# Connectors.net
KiCad netlist of a schematic drawn in Altium Designer
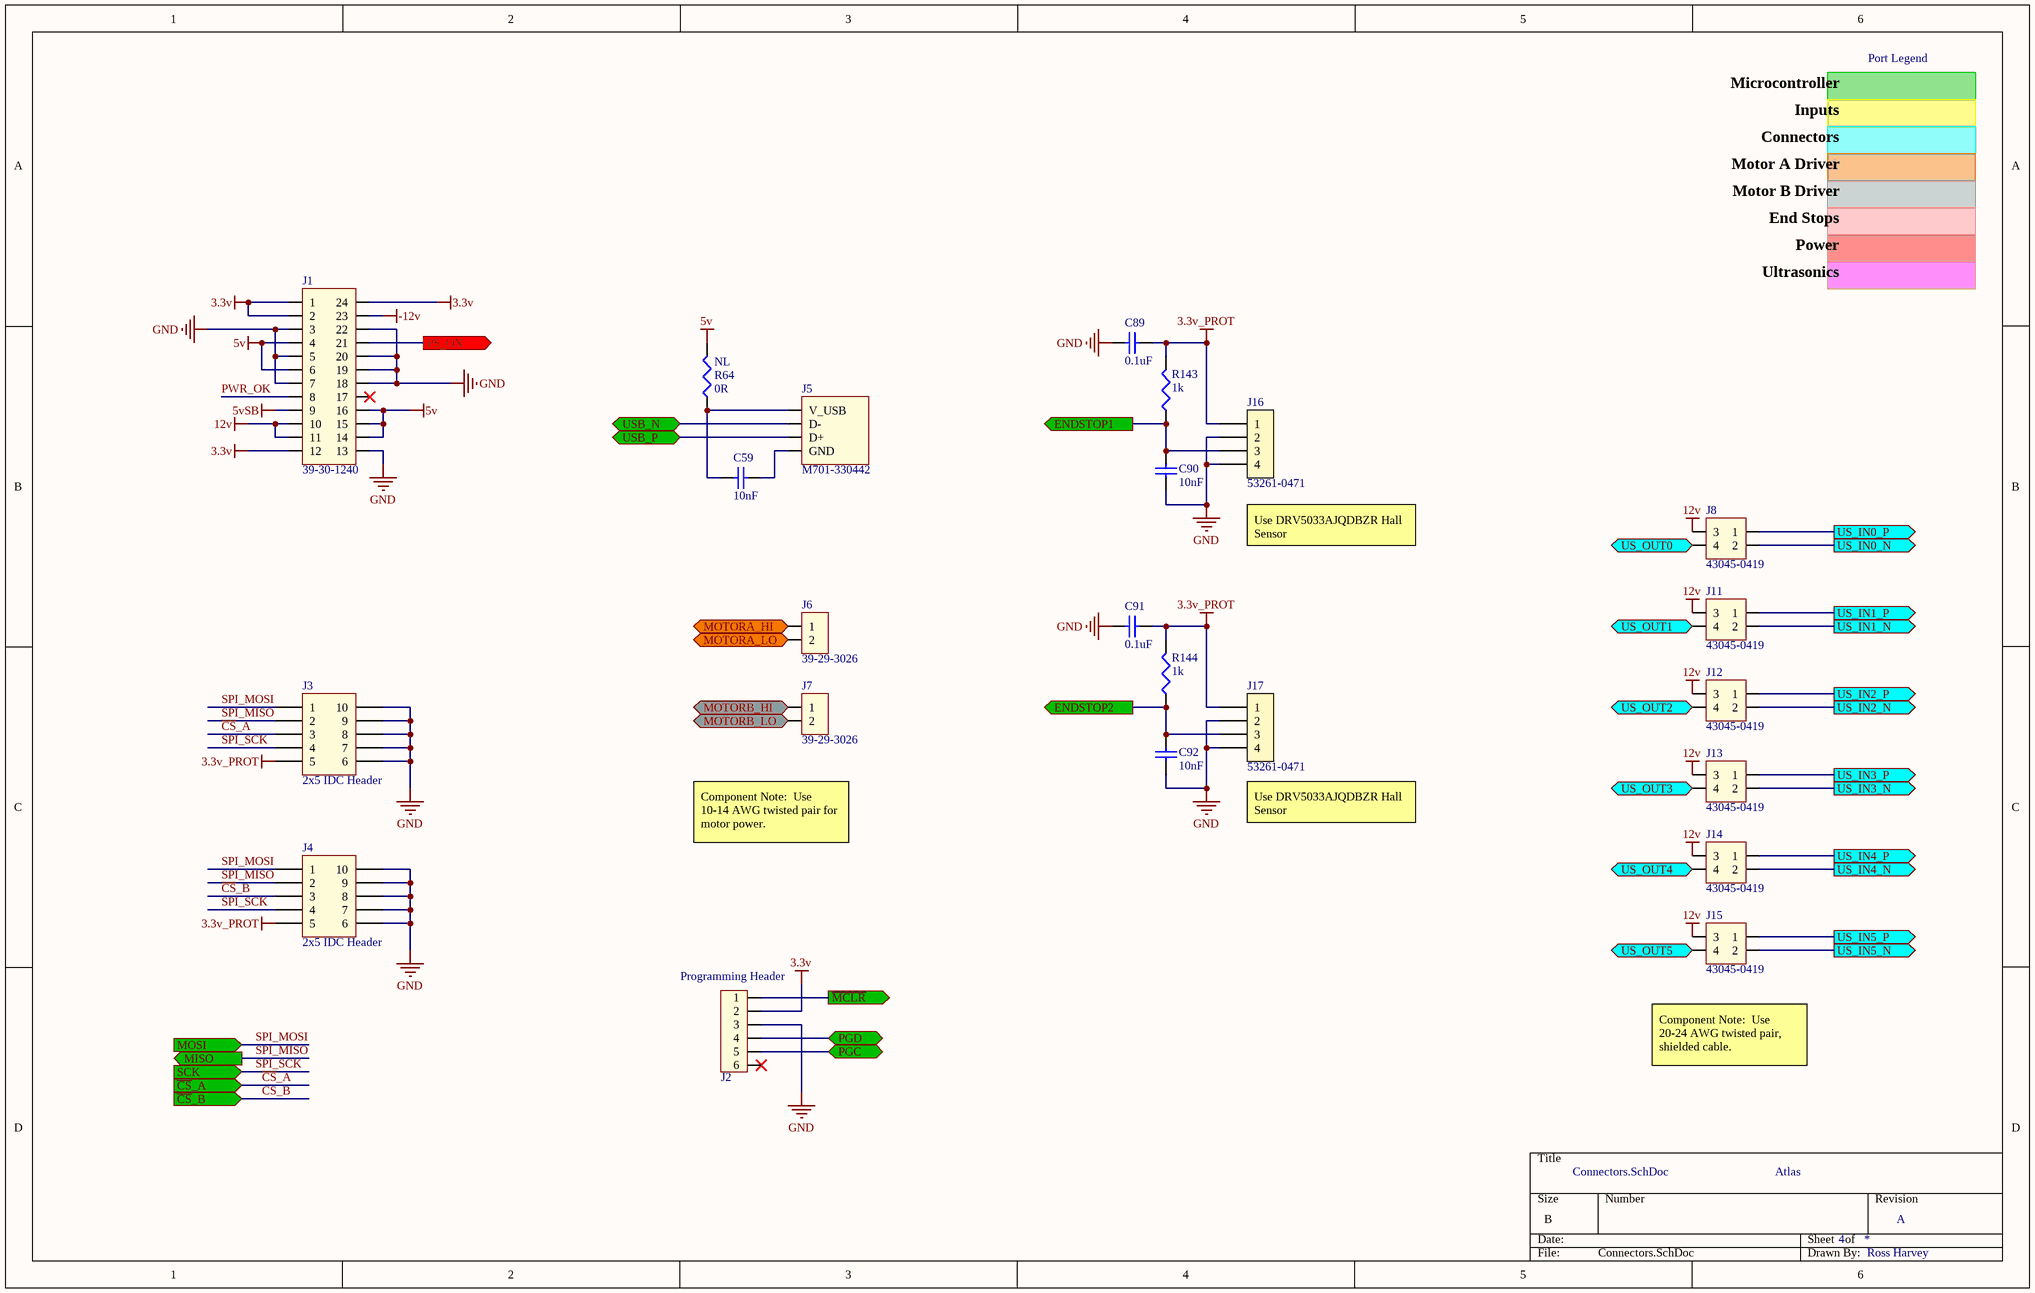
[diagram p0: Connectors.SchDoc]

(export (version "E")
  (design (tool "Eeschema 10.0.6"))
  (components
    (comp (ref "C59") (value "10nF") (footprint "CAP0603W") (libsource (lib "Altium Library") (part "10nF")))
    (comp (ref "C89")
      (value "0.1uF")
      (footprint "CAP0603W")
      (libsource (lib "Altium Library") (part "0.1uF"))
    )
    (comp (ref "C90") (value "10nF") (footprint "CAP0603W") (libsource (lib "Altium Library") (part "10nF")))
    (comp (ref "C91")
      (value "0.1uF")
      (footprint "CAP0603W")
      (libsource (lib "Altium Library") (part "0.1uF"))
    )
    (comp (ref "C92") (value "10nF") (footprint "CAP0603W") (libsource (lib "Altium Library") (part "10nF")))
    (comp (ref "J1")
      (value "39-30-1240")
      (footprint "MOLEX 39-30-1240")
      (description "Male Connector for ATX Power Supply")
      (fields (field (name "MFG") "MOLEX"))
      (libsource (lib "Altium Library") (part "Molex_39-30-1240"))
    )
    (comp (ref "J2")
      (value "1x6 Header")
      (footprint "1x6 Header")
      (description "1x6 Header, 2.52mm pitch")
      (libsource (lib "Altium Library") (part "1x6 Header"))
    )
    (comp (ref "J3")
      (value "87831-1010")
      (footprint "MOLEX_87831-1010")
      (description "2x5 IDC Header")
      (fields (field (name "MFG") "MOLEX") (field (name "TYPE") "2x5 IDC Header"))
      (libsource (lib "Altium Library") (part "2x5 IDC/Ribbon Header"))
    )
    (comp (ref "J4")
      (value "87831-1010")
      (footprint "MOLEX_87831-1010")
      (description "2x5 IDC Header")
      (fields (field (name "MFG") "MOLEX") (field (name "TYPE") "2x5 IDC Header"))
      (libsource (lib "Altium Library") (part "2x5 IDC/Ribbon Header"))
    )
    (comp (ref "J5")
      (value "M701-330442")
      (footprint "M701-330442")
      (description "Board Mounted Vertical USB B-Type Plug")
      (fields (field (name "MFG") "HARWIN"))
      (libsource (lib "Altium Library") (part "USB Vertical Connector"))
    )
    (comp (ref "J6")
      (value "39-29-3026")
      (footprint "1x2 MicroFit")
      (description "1x2 MicroFit")
      (fields (field (name "MFG") "MOLEX"))
      (libsource (lib "Altium Library") (part "1x2 Microfit"))
    )
    (comp (ref "J7")
      (value "39-29-3026")
      (footprint "1x2 MicroFit")
      (description "1x2 MicroFit")
      (fields (field (name "MFG") "MOLEX"))
      (libsource (lib "Altium Library") (part "1x2 Microfit"))
    )
    (comp (ref "J8")
      (value "43045-0419")
      (footprint "MicroFit 2x2")
      (description "2x2 MicroFit")
      (fields (field (name "MFG") "MOLEX"))
      (libsource (lib "Altium Library") (part "2x2 Microfit"))
    )
    (comp (ref "J11")
      (value "43045-0419")
      (footprint "MicroFit 2x2")
      (description "2x2 MicroFit")
      (fields (field (name "MFG") "MOLEX"))
      (libsource (lib "Altium Library") (part "2x2 Microfit"))
    )
    (comp (ref "J12")
      (value "43045-0419")
      (footprint "MicroFit 2x2")
      (description "2x2 MicroFit")
      (fields (field (name "MFG") "MOLEX"))
      (libsource (lib "Altium Library") (part "2x2 Microfit"))
    )
    (comp (ref "J13")
      (value "43045-0419")
      (footprint "MicroFit 2x2")
      (description "2x2 MicroFit")
      (fields (field (name "MFG") "MOLEX"))
      (libsource (lib "Altium Library") (part "2x2 Microfit"))
    )
    (comp (ref "J14")
      (value "43045-0419")
      (footprint "MicroFit 2x2")
      (description "2x2 MicroFit")
      (fields (field (name "MFG") "MOLEX"))
      (libsource (lib "Altium Library") (part "2x2 Microfit"))
    )
    (comp (ref "J15")
      (value "43045-0419")
      (footprint "MicroFit 2x2")
      (description "2x2 MicroFit")
      (fields (field (name "MFG") "MOLEX"))
      (libsource (lib "Altium Library") (part "2x2 Microfit"))
    )
    (comp (ref "J16")
      (value "53261-0471")
      (footprint "1x4 PicoBlade")
      (description "1x4 PicoBlade, 1.25mm Pitch, SMD")
      (fields (field (name "MFG") "MOLEX"))
      (libsource (lib "Altium Library") (part "1x4 PicoBlade"))
    )
    (comp (ref "J17")
      (value "53261-0471")
      (footprint "1x4 PicoBlade")
      (description "1x4 PicoBlade, 1.25mm Pitch, SMD")
      (fields (field (name "MFG") "MOLEX"))
      (libsource (lib "Altium Library") (part "1x4 PicoBlade"))
    )
    (comp (ref "R64")
      (value "0R")
      (footprint "RES0603W")
      (fields (field (name "MFG") "Vishay") (field (name "LOAD") "NL"))
      (libsource (lib "Altium Library") (part "0R (0603)"))
    )
    (comp (ref "R143")
      (value "1k")
      (footprint "RES0603W")
      (fields (field (name "TOLERANCE") "1%") (field (name "POWER") "0.1W") (field (name "MFG") "Vishay"))
      (libsource (lib "Altium Library") (part "1k (0603)"))
    )
    (comp (ref "R144")
      (value "1k")
      (footprint "RES0603W")
      (fields (field (name "TOLERANCE") "1%") (field (name "POWER") "0.1W") (field (name "MFG") "Vishay"))
      (libsource (lib "Altium Library") (part "1k (0603)"))
    )
  )
  (nets
    (net (code "1") (name "-12v") (class "Default")
      (node (ref "J1") (pin "23") (pinfunction "23_23") (pintype "passive"))
    )
    (net (code "2") (name "/ENDSTOP1") (class "Default")
      (node (ref "C90") (pin "1") (pinfunction "1_1") (pintype "passive"))
      (node (ref "J16") (pin "3") (pinfunction "3_3") (pintype "passive"))
      (node (ref "R143") (pin "1") (pinfunction "1_1") (pintype "passive"))
    )
    (net (code "3") (name "/ENDSTOP2") (class "Default")
      (node (ref "C92") (pin "1") (pinfunction "1_1") (pintype "passive"))
      (node (ref "J17") (pin "3") (pinfunction "3_3") (pintype "passive"))
      (node (ref "R144") (pin "1") (pinfunction "1_1") (pintype "passive"))
    )
    (net (code "4") (name "/MOTORA_HI") (class "Default")
      (node (ref "J6") (pin "1") (pinfunction "1_1") (pintype "passive"))
    )
    (net (code "5") (name "/MOTORA_LO") (class "Default")
      (node (ref "J6") (pin "2") (pinfunction "2_2") (pintype "passive"))
    )
    (net (code "6") (name "/MOTORB_HI") (class "Default")
      (node (ref "J7") (pin "1") (pinfunction "1_1") (pintype "passive"))
    )
    (net (code "7") (name "/MOTORB_LO") (class "Default")
      (node (ref "J7") (pin "2") (pinfunction "2_2") (pintype "passive"))
    )
    (net (code "8") (name "/PGC") (class "Default")
      (node (ref "J2") (pin "5") (pinfunction "5_5") (pintype "passive"))
    )
    (net (code "9") (name "/PGD") (class "Default")
      (node (ref "J2") (pin "4") (pinfunction "4_4") (pintype "passive"))
    )
    (net (code "10") (name "/PS_ON") (class "Default")
      (node (ref "J1") (pin "21") (pinfunction "21_21") (pintype "passive"))
    )
    (net (code "11") (name "/PWR_OK") (class "Default")
      (node (ref "J1") (pin "8") (pinfunction "8_8") (pintype "passive"))
    )
    (net (code "12") (name "/SPI_MISO") (class "Default")
      (node (ref "J3") (pin "2") (pinfunction "2_2") (pintype "passive"))
      (node (ref "J4") (pin "2") (pinfunction "2_2") (pintype "passive"))
    )
    (net (code "13") (name "/SPI_MOSI") (class "Default")
      (node (ref "J3") (pin "1") (pinfunction "1_1") (pintype "passive"))
      (node (ref "J4") (pin "1") (pinfunction "1_1") (pintype "passive"))
    )
    (net (code "14") (name "/SPI_SCK") (class "Default")
      (node (ref "J3") (pin "4") (pinfunction "4_4") (pintype "passive"))
      (node (ref "J4") (pin "4") (pinfunction "4_4") (pintype "passive"))
    )
    (net (code "15") (name "/USB_N") (class "Default")
      (node (ref "J5") (pin "2") (pinfunction "D-_2") (pintype "passive"))
    )
    (net (code "16") (name "/USB_P") (class "Default")
      (node (ref "J5") (pin "3") (pinfunction "D+_3") (pintype "passive"))
    )
    (net (code "17") (name "/US_IN0_N") (class "Default")
      (node (ref "J8") (pin "2") (pinfunction "2_2") (pintype "passive"))
    )
    (net (code "18") (name "/US_IN0_P") (class "Default")
      (node (ref "J8") (pin "1") (pinfunction "1_1") (pintype "passive"))
    )
    (net (code "19") (name "/US_IN1_N") (class "Default")
      (node (ref "J11") (pin "2") (pinfunction "2_2") (pintype "passive"))
    )
    (net (code "20") (name "/US_IN1_P") (class "Default")
      (node (ref "J11") (pin "1") (pinfunction "1_1") (pintype "passive"))
    )
    (net (code "21") (name "/US_IN2_N") (class "Default")
      (node (ref "J12") (pin "2") (pinfunction "2_2") (pintype "passive"))
    )
    (net (code "22") (name "/US_IN2_P") (class "Default")
      (node (ref "J12") (pin "1") (pinfunction "1_1") (pintype "passive"))
    )
    (net (code "23") (name "/US_IN3_N") (class "Default")
      (node (ref "J13") (pin "2") (pinfunction "2_2") (pintype "passive"))
    )
    (net (code "24") (name "/US_IN3_P") (class "Default")
      (node (ref "J13") (pin "1") (pinfunction "1_1") (pintype "passive"))
    )
    (net (code "25") (name "/US_IN4_N") (class "Default")
      (node (ref "J14") (pin "2") (pinfunction "2_2") (pintype "passive"))
    )
    (net (code "26") (name "/US_IN4_P") (class "Default")
      (node (ref "J14") (pin "1") (pinfunction "1_1") (pintype "passive"))
    )
    (net (code "27") (name "/US_IN5_N") (class "Default")
      (node (ref "J15") (pin "2") (pinfunction "2_2") (pintype "passive"))
    )
    (net (code "28") (name "/US_IN5_P") (class "Default")
      (node (ref "J15") (pin "1") (pinfunction "1_1") (pintype "passive"))
    )
    (net (code "29") (name "/US_OUT0") (class "Default")
      (node (ref "J8") (pin "4") (pinfunction "4_4") (pintype "passive"))
    )
    (net (code "30") (name "/US_OUT1") (class "Default")
      (node (ref "J11") (pin "4") (pinfunction "4_4") (pintype "passive"))
    )
    (net (code "31") (name "/US_OUT2") (class "Default")
      (node (ref "J12") (pin "4") (pinfunction "4_4") (pintype "passive"))
    )
    (net (code "32") (name "/US_OUT3") (class "Default")
      (node (ref "J13") (pin "4") (pinfunction "4_4") (pintype "passive"))
    )
    (net (code "33") (name "/US_OUT4") (class "Default")
      (node (ref "J14") (pin "4") (pinfunction "4_4") (pintype "passive"))
    )
    (net (code "34") (name "/US_OUT5") (class "Default")
      (node (ref "J15") (pin "4") (pinfunction "4_4") (pintype "passive"))
    )
    (net (code "35") (name "/~{CS}_A") (class "Default")
      (node (ref "J3") (pin "3") (pinfunction "3_3") (pintype "passive"))
    )
    (net (code "36") (name "/~{CS}_B") (class "Default")
      (node (ref "J4") (pin "3") (pinfunction "3_3") (pintype "passive"))
    )
    (net (code "37") (name "/~{MCLR}") (class "Default")
      (node (ref "J2") (pin "1") (pinfunction "1_1") (pintype "passive"))
    )
    (net (code "38") (name "3.3v") (class "Default")
      (node (ref "J1") (pin "1") (pinfunction "1_1") (pintype "passive"))
      (node (ref "J1") (pin "12") (pinfunction "12_12") (pintype "passive"))
      (node (ref "J1") (pin "2") (pinfunction "2_2") (pintype "passive"))
      (node (ref "J1") (pin "24") (pinfunction "24_24") (pintype "passive"))
      (node (ref "J2") (pin "2") (pinfunction "2_2") (pintype "passive"))
    )
    (net (code "39") (name "3.3v_PROT") (class "Default")
      (node (ref "C89") (pin "1") (pinfunction "1_1") (pintype "passive"))
      (node (ref "C91") (pin "1") (pinfunction "1_1") (pintype "passive"))
      (node (ref "J16") (pin "1") (pinfunction "1_1") (pintype "passive"))
      (node (ref "J17") (pin "1") (pinfunction "1_1") (pintype "passive"))
      (node (ref "J3") (pin "5") (pinfunction "5_5") (pintype "passive"))
      (node (ref "J4") (pin "5") (pinfunction "5_5") (pintype "passive"))
      (node (ref "R143") (pin "2") (pinfunction "2_2") (pintype "passive"))
      (node (ref "R144") (pin "2") (pinfunction "2_2") (pintype "passive"))
    )
    (net (code "40") (name "5v") (class "Default")
      (node (ref "J1") (pin "14") (pinfunction "14_14") (pintype "passive"))
      (node (ref "J1") (pin "15") (pinfunction "15_15") (pintype "passive"))
      (node (ref "J1") (pin "16") (pinfunction "16_16") (pintype "passive"))
      (node (ref "J1") (pin "4") (pinfunction "4_4") (pintype "passive"))
      (node (ref "J1") (pin "6") (pinfunction "6_6") (pintype "passive"))
      (node (ref "R64") (pin "2") (pinfunction "2_2") (pintype "passive"))
    )
    (net (code "41") (name "5vSB") (class "Default")
      (node (ref "J1") (pin "9") (pinfunction "9_9") (pintype "passive"))
    )
    (net (code "42") (name "12v") (class "Default")
      (node (ref "J1") (pin "10") (pinfunction "10_10") (pintype "passive"))
      (node (ref "J1") (pin "11") (pinfunction "11_11") (pintype "passive"))
      (node (ref "J11") (pin "3") (pinfunction "3_3") (pintype "passive"))
      (node (ref "J12") (pin "3") (pinfunction "3_3") (pintype "passive"))
      (node (ref "J13") (pin "3") (pinfunction "3_3") (pintype "passive"))
      (node (ref "J14") (pin "3") (pinfunction "3_3") (pintype "passive"))
      (node (ref "J15") (pin "3") (pinfunction "3_3") (pintype "passive"))
      (node (ref "J8") (pin "3") (pinfunction "3_3") (pintype "passive"))
    )
    (net (code "43") (name "GND") (class "Default")
      (node (ref "C89") (pin "2") (pinfunction "2_2") (pintype "passive"))
      (node (ref "C90") (pin "2") (pinfunction "2_2") (pintype "passive"))
      (node (ref "C91") (pin "2") (pinfunction "2_2") (pintype "passive"))
      (node (ref "C92") (pin "2") (pinfunction "2_2") (pintype "passive"))
      (node (ref "J1") (pin "13") (pinfunction "13_13") (pintype "passive"))
      (node (ref "J1") (pin "18") (pinfunction "18_18") (pintype "passive"))
      (node (ref "J1") (pin "19") (pinfunction "19_19") (pintype "passive"))
      (node (ref "J1") (pin "20") (pinfunction "20_20") (pintype "passive"))
      (node (ref "J1") (pin "22") (pinfunction "22_22") (pintype "passive"))
      (node (ref "J1") (pin "3") (pinfunction "3_3") (pintype "passive"))
      (node (ref "J1") (pin "5") (pinfunction "5_5") (pintype "passive"))
      (node (ref "J1") (pin "7") (pinfunction "7_7") (pintype "passive"))
      (node (ref "J16") (pin "2") (pinfunction "2_2") (pintype "passive"))
      (node (ref "J16") (pin "4") (pinfunction "4_4") (pintype "passive"))
      (node (ref "J17") (pin "2") (pinfunction "2_2") (pintype "passive"))
      (node (ref "J17") (pin "4") (pinfunction "4_4") (pintype "passive"))
      (node (ref "J2") (pin "3") (pinfunction "3_3") (pintype "passive"))
      (node (ref "J3") (pin "10") (pinfunction "10_10") (pintype "passive"))
      (node (ref "J3") (pin "6") (pinfunction "6_6") (pintype "passive"))
      (node (ref "J3") (pin "7") (pinfunction "7_7") (pintype "passive"))
      (node (ref "J3") (pin "8") (pinfunction "8_8") (pintype "passive"))
      (node (ref "J3") (pin "9") (pinfunction "9_9") (pintype "passive"))
      (node (ref "J4") (pin "10") (pinfunction "10_10") (pintype "passive"))
      (node (ref "J4") (pin "6") (pinfunction "6_6") (pintype "passive"))
      (node (ref "J4") (pin "7") (pinfunction "7_7") (pintype "passive"))
      (node (ref "J4") (pin "8") (pinfunction "8_8") (pintype "passive"))
      (node (ref "J4") (pin "9") (pinfunction "9_9") (pintype "passive"))
    )
    (net (code "44") (name "Net-(J5-GND)") (class "Default")
      (node (ref "C59") (pin "2") (pinfunction "2_2") (pintype "passive"))
      (node (ref "J5") (pin "4") (pinfunction "GND_4") (pintype "passive"))
    )
    (net (code "45") (name "Net-(J5-V_USB)") (class "Default")
      (node (ref "C59") (pin "1") (pinfunction "1_1") (pintype "passive"))
      (node (ref "J5") (pin "1") (pinfunction "V_USB_1") (pintype "passive"))
      (node (ref "R64") (pin "1") (pinfunction "1_1") (pintype "passive"))
    )
    (net (code "46") (name "unconnected-(J1-Pad17)") (class "Default")
      (node (ref "J1") (pin "17") (pinfunction "17_17") (pintype "passive+no_connect"))
    )
    (net (code "47") (name "unconnected-(J2-Pad6)") (class "Default")
      (node (ref "J2") (pin "6") (pinfunction "6_6") (pintype "passive+no_connect"))
    )
  )
)
